# PX4FMUv2_4_6_03.net
KiCad netlist of a schematic drawn in Altium Designer
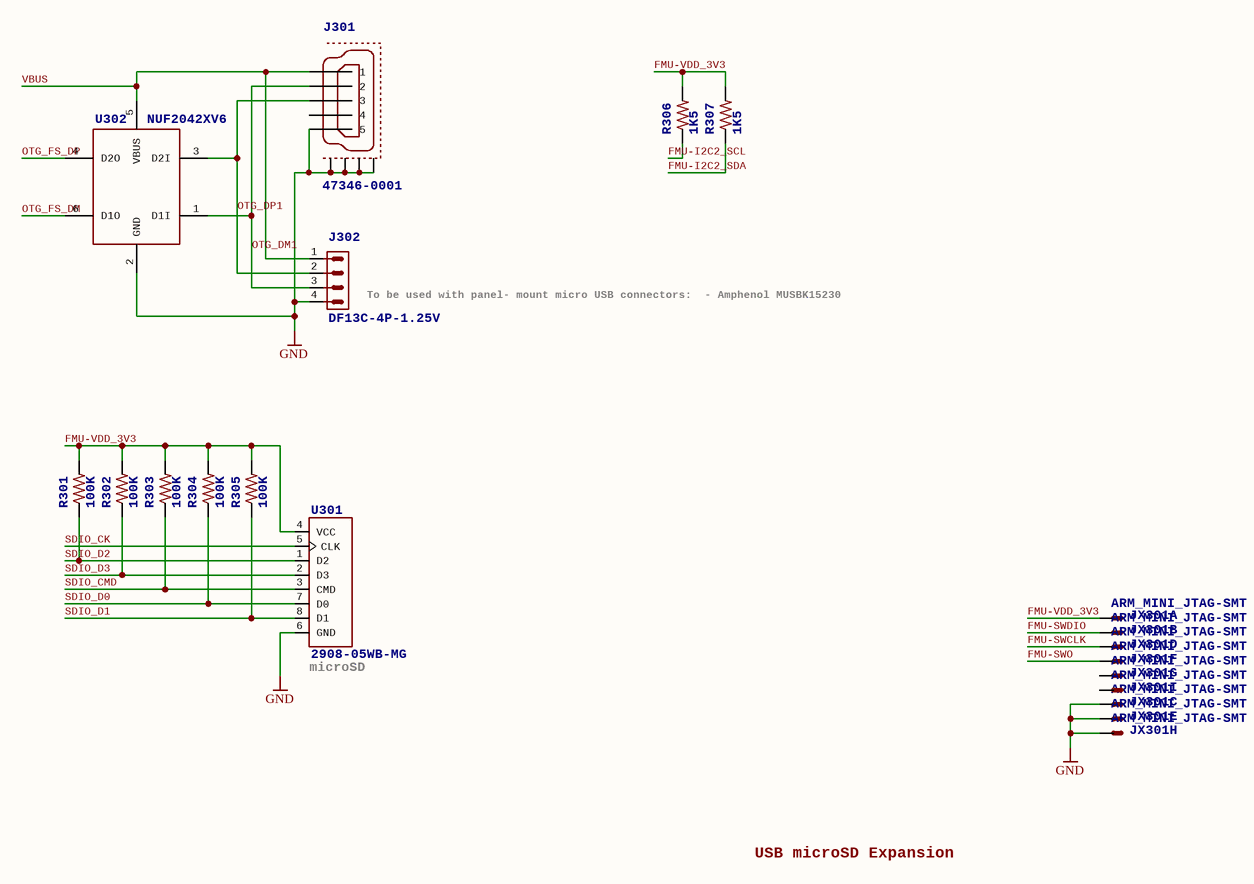
[diagram p0: PX4FMUv2.4.6_03.SchDoc]

(export (version "E")
  (design (tool "Eeschema 10.0.6"))
  (components
    (comp (ref "J301")
      (value "47346-0001")
      (footprint "MOLEX-47346-0001")
      (description "MICRO USB B, BOTTOM MOUNT")
      (libsource (lib "pixhawk2") (part "MOLEX-47346-0001"))
    )
    (comp (ref "J302")
      (value "DF13C-4P-1.25V")
      (footprint "DF13C-4P-1.25V")
      (description "DF13-4P\n1.25mm Pitch Miniature Crimping Connector.")
      (fields (field (name "PARTNO") "DF13C-4P-1.25V(20)"))
      (libsource (lib "con-hirose-df13") (part "DF13-4P-1.25V"))
    )
    (comp (ref "JX301")
      (value "ARM_MINI_JTAG-SMT")
      (footprint "FTSH-105-01-XXX-DV-K")
      (description "<b>CONNECTOR</b><p>\nwire to board 1.25 mm (.049 inch) pitch header")
      (fields (field (name "PARTNO") "M50-3900542"))
      (libsource (lib "pixhawk2") (part "ARM_MINI_JTAG-SMT"))
    )
    (comp (ref "R301")
      (value "100K")
      (footprint "0402-RES")
      (fields (field (name "PARTNO") "RC0402FR-07100KL"))
      (libsource (lib "pixhawk2") (part "RESISTOR0402-RES"))
    )
    (comp (ref "R302")
      (value "100K")
      (footprint "0402-RES")
      (fields (field (name "PARTNO") "RC0402FR-07100KL"))
      (libsource (lib "pixhawk2") (part "RESISTOR0402-RES"))
    )
    (comp (ref "R303")
      (value "100K")
      (footprint "0402-RES")
      (fields (field (name "PARTNO") "RC0402FR-07100KL"))
      (libsource (lib "pixhawk2") (part "RESISTOR0402-RES"))
    )
    (comp (ref "R304")
      (value "100K")
      (footprint "0402-RES")
      (fields (field (name "PARTNO") "RC0402FR-07100KL"))
      (libsource (lib "pixhawk2") (part "RESISTOR0402-RES"))
    )
    (comp (ref "R305")
      (value "100K")
      (footprint "0402-RES")
      (fields (field (name "PARTNO") "RC0402FR-07100KL"))
      (libsource (lib "pixhawk2") (part "RESISTOR0402-RES"))
    )
    (comp (ref "R306")
      (value "1K5")
      (footprint "0402-RES")
      (fields (field (name "PARTNO") "RC0402FR-071K5L"))
      (libsource (lib "pixhawk2") (part "RESISTOR0402-RES"))
    )
    (comp (ref "R307")
      (value "1K5")
      (footprint "0402-RES")
      (fields (field (name "PARTNO") "RC0402FR-071K5L"))
      (libsource (lib "pixhawk2") (part "RESISTOR0402-RES"))
    )
    (comp (ref "U301")
      (value "2908-05WB-MG")
      (footprint "MICROSD")
      (libsource (lib "baseboard") (part "MICROSDSDI"))
    )
    (comp (ref "U302")
      (value "NUF2042XV6")
      (footprint "SOT563-6")
      (fields (field (name "PARTNO") "NUF2042XV6T1G"))
      (libsource (lib "pixhawk2") (part "NUF2042XV6"))
    )
  )
  (nets
    (net (code "1") (name "/FMU-I2C2_SCL") (class "Default")
      (node (ref "R306") (pin "P$1") (pinfunction "1_P$1") (pintype "passive"))
    )
    (net (code "2") (name "/FMU-I2C2_SDA") (class "Default")
      (node (ref "R307") (pin "P$1") (pinfunction "1_P$1") (pintype "passive"))
    )
    (net (code "3") (name "/FMU-SWCLK") (class "Default")
      (node (ref "JX301") (pin "4") (pinfunction "S_4") (pintype "passive"))
    )
    (net (code "4") (name "/FMU-SWDIO") (class "Default")
      (node (ref "JX301") (pin "2") (pinfunction "S_2") (pintype "passive"))
    )
    (net (code "5") (name "/FMU-SWO") (class "Default")
      (node (ref "JX301") (pin "6") (pinfunction "S_6") (pintype "passive"))
    )
    (net (code "6") (name "/FMU-VDD_3V3") (class "Default")
      (node (ref "JX301") (pin "1") (pinfunction "S_1") (pintype "passive"))
      (node (ref "R301") (pin "P$2") (pinfunction "2_P$2") (pintype "passive"))
      (node (ref "R302") (pin "P$2") (pinfunction "2_P$2") (pintype "passive"))
      (node (ref "R303") (pin "P$2") (pinfunction "2_P$2") (pintype "passive"))
      (node (ref "R304") (pin "P$2") (pinfunction "2_P$2") (pintype "passive"))
      (node (ref "R305") (pin "P$2") (pinfunction "2_P$2") (pintype "passive"))
      (node (ref "R306") (pin "P$2") (pinfunction "2_P$2") (pintype "passive"))
      (node (ref "R307") (pin "P$2") (pinfunction "2_P$2") (pintype "passive"))
      (node (ref "U301") (pin "4") (pinfunction "VCC_4") (pintype "passive"))
    )
    (net (code "7") (name "/OTG_DM1") (class "Default")
      (node (ref "J301") (pin "D-") (pinfunction "2_D-") (pintype "passive"))
      (node (ref "J302") (pin "3") (pinfunction "3_3") (pintype "passive"))
      (node (ref "U302") (pin "1") (pinfunction "D1I_1") (pintype "passive"))
    )
    (net (code "8") (name "/OTG_DP1") (class "Default")
      (node (ref "J301") (pin "D+") (pinfunction "3_D+") (pintype "passive"))
      (node (ref "J302") (pin "2") (pinfunction "2_2") (pintype "passive"))
      (node (ref "U302") (pin "3") (pinfunction "D2I_3") (pintype "passive"))
    )
    (net (code "9") (name "/OTG_FS_DM") (class "Default")
      (node (ref "U302") (pin "6") (pinfunction "D1O_6") (pintype "passive"))
    )
    (net (code "10") (name "/OTG_FS_DP") (class "Default")
      (node (ref "U302") (pin "4") (pinfunction "D2O_4") (pintype "passive"))
    )
    (net (code "11") (name "/SDIO_CK") (class "Default")
      (node (ref "U301") (pin "5") (pinfunction "CLK_5") (pintype "passive"))
    )
    (net (code "12") (name "/SDIO_CMD") (class "Default")
      (node (ref "R303") (pin "P$1") (pinfunction "1_P$1") (pintype "passive"))
      (node (ref "U301") (pin "3") (pinfunction "CMD_3") (pintype "passive"))
    )
    (net (code "13") (name "/SDIO_D0") (class "Default")
      (node (ref "R304") (pin "P$1") (pinfunction "1_P$1") (pintype "passive"))
      (node (ref "U301") (pin "7") (pinfunction "D0_7") (pintype "passive"))
    )
    (net (code "14") (name "/SDIO_D1") (class "Default")
      (node (ref "R305") (pin "P$1") (pinfunction "1_P$1") (pintype "passive"))
      (node (ref "U301") (pin "8") (pinfunction "D1_8") (pintype "passive"))
    )
    (net (code "15") (name "/SDIO_D2") (class "Default")
      (node (ref "R301") (pin "P$1") (pinfunction "1_P$1") (pintype "passive"))
      (node (ref "U301") (pin "1") (pinfunction "D2_1") (pintype "passive"))
    )
    (net (code "16") (name "/SDIO_D3") (class "Default")
      (node (ref "R302") (pin "P$1") (pinfunction "1_P$1") (pintype "passive"))
      (node (ref "U301") (pin "2") (pinfunction "D3_2") (pintype "passive"))
    )
    (net (code "17") (name "/VBUS") (class "Default")
      (node (ref "J301") (pin "VBUS") (pinfunction "1_VBUS") (pintype "open_emitter"))
      (node (ref "J302") (pin "1") (pinfunction "1_1") (pintype "passive"))
      (node (ref "U302") (pin "5") (pinfunction "VBUS_5") (pintype "passive"))
    )
    (net (code "18") (name "GND") (class "Default")
      (node (ref "J301") (pin "GND") (pinfunction "5_GND") (pintype "open_emitter"))
      (node (ref "J301") (pin "GND1") (pinfunction "GND1_GND1") (pintype "passive"))
      (node (ref "J301") (pin "GND2") (pinfunction "GND2_GND2") (pintype "passive"))
      (node (ref "J301") (pin "GND3") (pinfunction "GND3_GND3") (pintype "passive"))
      (node (ref "J301") (pin "GND4") (pinfunction "GND4_GND4") (pintype "passive"))
      (node (ref "J302") (pin "4") (pinfunction "4_4") (pintype "passive"))
      (node (ref "JX301") (pin "3") (pinfunction "S_3") (pintype "passive"))
      (node (ref "JX301") (pin "5") (pinfunction "S_5") (pintype "passive"))
      (node (ref "JX301") (pin "9") (pinfunction "S_9") (pintype "passive"))
      (node (ref "U301") (pin "6") (pinfunction "GND_6") (pintype "open_emitter"))
      (node (ref "U302") (pin "2") (pinfunction "GND_2") (pintype "passive"))
    )
    (net (code "19") (name "unconnected-(J301-4-PadID)") (class "Default")
      (node (ref "J301") (pin "ID") (pinfunction "4_ID") (pintype "passive"))
    )
    (net (code "20") (name "unconnected-(JX301G-S-Pad8)") (class "Default")
      (node (ref "JX301") (pin "8") (pinfunction "S_8") (pintype "passive"))
    )
    (net (code "21") (name "unconnected-(JX301I-S-Pad10)") (class "Default")
      (node (ref "JX301") (pin "10") (pinfunction "S_10") (pintype "passive"))
    )
  )
)
